# POWER-DCDC.net
KiCad netlist of a schematic drawn in EAGLE
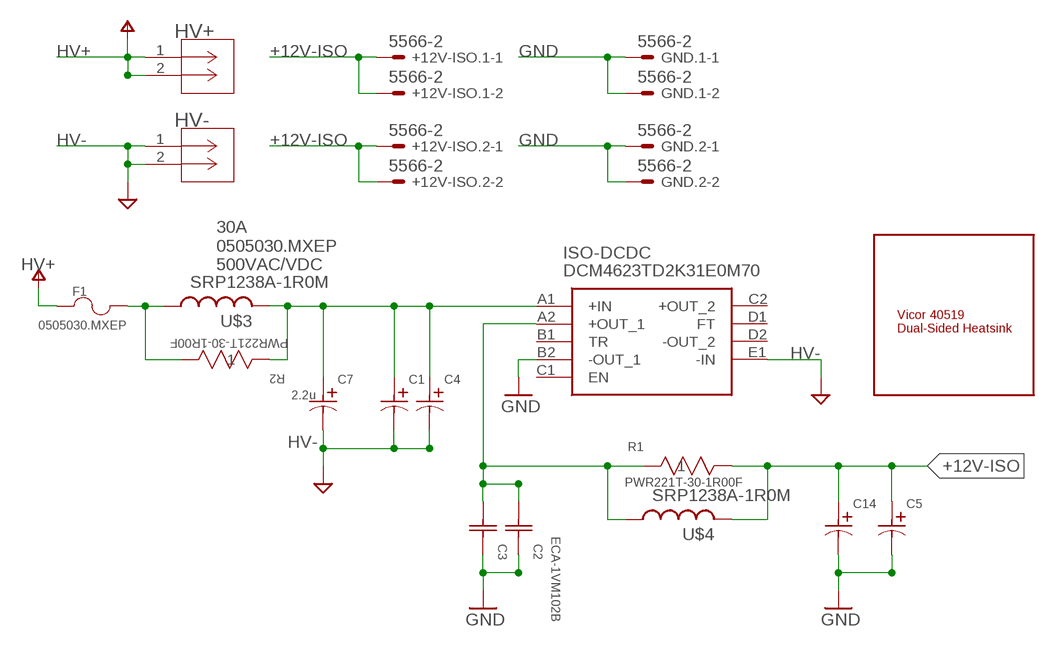
[diagram p0: schematic, sheet 1]

(export (version "E")
  (design (tool "Eeschema 10.0.6"))
  (components
    (comp (ref "+12V-ISO.1")
      (value "5566-2")
      (footprint "eagle-import:5566-2")
      (fields (field (name "MF") "MOLEX"))
      (libsource (lib "eagle-import") (part "5566-2"))
    )
    (comp (ref "+12V-ISO.2")
      (value "5566-2")
      (footprint "eagle-import:5566-2")
      (fields (field (name "MF") "MOLEX"))
      (libsource (lib "eagle-import") (part "5566-2"))
    )
    (comp (ref "C1")
      (value "ECA-2WHG2R2")
      (footprint "eagle-import:PCAP_10X125")
      (fields (field (name "MANUFACTURER_PART_NUMBER") "ECA2WHG2R2"))
      (libsource (lib "eagle-import") (part "ECA-2WHG2R2"))
    )
    (comp (ref "C2")
      (value "ECA-1VM102B")
      (footprint "eagle-import:CAP_PAN_12.5X20")
      (fields (field (name "MANUFACTURER_PART_NUMBER") "ECA1VM102B"))
      (libsource (lib "eagle-import") (part "ECA-1VM102B"))
    )
    (comp (ref "C3")
      (value "ECA-1VM102B")
      (footprint "eagle-import:CAP_PAN_12.5X20")
      (fields (field (name "MANUFACTURER_PART_NUMBER") "ECA1VM102B"))
      (libsource (lib "eagle-import") (part "ECA-1VM102B"))
    )
    (comp (ref "C4")
      (value "ECA-2WHG2R2")
      (footprint "eagle-import:PCAP_10X125")
      (fields (field (name "MANUFACTURER_PART_NUMBER") "ECA2WHG2R2"))
      (libsource (lib "eagle-import") (part "ECA-2WHG2R2"))
    )
    (comp (ref "C5")
      (value "ECA-2WHG2R2")
      (footprint "eagle-import:PCAP_10X125")
      (fields (field (name "MANUFACTURER_PART_NUMBER") "ECA2WHG2R2"))
      (libsource (lib "eagle-import") (part "ECA-2WHG2R2"))
    )
    (comp (ref "C7")
      (value "2.2u")
      (footprint "eagle-import:PCAP_10X125")
      (fields (field (name "MANUFACTURER_PART_NUMBER") "ECA2WHG2R2"))
      (libsource (lib "eagle-import") (part "ECA-2WHG2R2"))
    )
    (comp (ref "C14")
      (value "ECA-2WHG2R2")
      (footprint "eagle-import:PCAP_10X125")
      (fields (field (name "MANUFACTURER_PART_NUMBER") "ECA2WHG2R2"))
      (libsource (lib "eagle-import") (part "ECA-2WHG2R2"))
    )
    (comp (ref "F1")
      (value "0505030.MXEP")
      (footprint "eagle-import:0505030.MXEP")
      (libsource (lib "eagle-import") (part "0505030.MXEP"))
    )
    (comp (ref "GND.1")
      (value "5566-2")
      (footprint "eagle-import:5566-2")
      (fields (field (name "MF") "MOLEX"))
      (libsource (lib "eagle-import") (part "5566-2"))
    )
    (comp (ref "GND.2")
      (value "5566-2")
      (footprint "eagle-import:5566-2")
      (fields (field (name "MF") "MOLEX"))
      (libsource (lib "eagle-import") (part "5566-2"))
    )
    (comp (ref "HEATSINK")
      (value "DCMHEATSINK")
      (footprint "eagle-import:DCMHEATSINK")
      (libsource (lib "eagle-import") (part "DCMHEATSINK"))
    )
    (comp (ref "HV+")
      (value "2P_1-770166-0")
      (footprint "eagle-import:CON2_1X2_P163_VMNL-1MTG")
      (fields (field (name "MANUFACTURER_PART_NUMBER") "17701660"))
      (libsource (lib "eagle-import") (part "2P_1-770166-0"))
    )
    (comp (ref "HV-")
      (value "2P_1-770166-0")
      (footprint "eagle-import:CON2_1X2_P163_VMNL-1MTG")
      (fields (field (name "MANUFACTURER_PART_NUMBER") "17701660"))
      (libsource (lib "eagle-import") (part "2P_1-770166-0"))
    )
    (comp (ref "ISO-DCDC")
      (value "DCM4623TD2K31E0M70")
      (footprint "eagle-import:DCM4623TD2N17C8T70")
      (fields (field (name "MOUSER_PART_NUMBER") "492-DCM4623D2K31E0M7"))
      (libsource (lib "eagle-import") (part "DCM4623TD2K31E0M70"))
    )
    (comp (ref "R1")
      (value "PWR221T-30-1R00F")
      (footprint "eagle-import:BO_PWR221T")
      (fields (field (name "MANUFACTURER_PART_NUMBER") "PWR221T301R00F"))
      (libsource (lib "eagle-import") (part "PWR221T-30-1R00F"))
    )
    (comp (ref "R2")
      (value "PWR221T-30-1R00F")
      (footprint "eagle-import:BO_PWR221T")
      (fields (field (name "MANUFACTURER_PART_NUMBER") "PWR221T301R00F"))
      (libsource (lib "eagle-import") (part "PWR221T-30-1R00F"))
    )
    (comp (ref "U$3")
      (value "SRP1238A-1R0M")
      (footprint "eagle-import:SRP1238A-R22M")
      (libsource (lib "eagle-import") (part "SRP1238A-1R0M"))
    )
    (comp (ref "U$4")
      (value "SRP1238A-1R0M")
      (footprint "eagle-import:SRP1238A-R22M")
      (libsource (lib "eagle-import") (part "SRP1238A-1R0M"))
    )
  )
  (nets
    (net (code "1") (name "+12V-ISO") (class "Default")
      (node (ref "+12V-ISO.1") (pin "1") (pinfunction "S_1") (pintype "passive"))
      (node (ref "+12V-ISO.1") (pin "2") (pinfunction "S_2") (pintype "passive"))
      (node (ref "+12V-ISO.2") (pin "1") (pinfunction "S_1") (pintype "passive"))
      (node (ref "+12V-ISO.2") (pin "2") (pinfunction "S_2") (pintype "passive"))
      (node (ref "C14") (pin "1") (pinfunction "1_1") (pintype "passive"))
      (node (ref "C5") (pin "1") (pinfunction "1_1") (pintype "passive"))
      (node (ref "R1") (pin "2") (pinfunction "2_2") (pintype "passive"))
      (node (ref "U$4") (pin "2") (pinfunction "2_2") (pintype "passive"))
    )
    (net (code "2") (name "AGND") (class "Default")
      (node (ref "C1") (pin "2") (pinfunction "2_2") (pintype "passive"))
      (node (ref "C4") (pin "2") (pinfunction "2_2") (pintype "passive"))
      (node (ref "C7") (pin "2") (pinfunction "2_2") (pintype "passive"))
      (node (ref "HV-") (pin "1") (pinfunction "1_1") (pintype "passive"))
      (node (ref "HV-") (pin "2") (pinfunction "2_2") (pintype "passive"))
      (node (ref "ISO-DCDC") (pin "E1") (pinfunction "-IN_E1") (pintype "bidirectional"))
    )
    (net (code "3") (name "GND") (class "Default")
      (node (ref "C14") (pin "2") (pinfunction "2_2") (pintype "passive"))
      (node (ref "C2") (pin "2") (pinfunction "2_2") (pintype "passive"))
      (node (ref "C3") (pin "2") (pinfunction "2_2") (pintype "passive"))
      (node (ref "C5") (pin "2") (pinfunction "2_2") (pintype "passive"))
      (node (ref "GND.1") (pin "1") (pinfunction "S_1") (pintype "passive"))
      (node (ref "GND.1") (pin "2") (pinfunction "S_2") (pintype "passive"))
      (node (ref "GND.2") (pin "1") (pinfunction "S_1") (pintype "passive"))
      (node (ref "GND.2") (pin "2") (pinfunction "S_2") (pintype "passive"))
      (node (ref "ISO-DCDC") (pin "B2") (pinfunction "-OUT_1_B2") (pintype "bidirectional"))
    )
    (net (code "4") (name "Net-(F1-Pad2)") (class "Default")
      (node (ref "F1") (pin "2") (pinfunction "2_2") (pintype "passive"))
      (node (ref "R2") (pin "2") (pinfunction "2_2") (pintype "passive"))
      (node (ref "U$3") (pin "1") (pinfunction "1_1") (pintype "passive"))
    )
    (net (code "5") (name "Net-(ISO-DCDC-+IN)") (class "Default")
      (node (ref "C1") (pin "1") (pinfunction "1_1") (pintype "passive"))
      (node (ref "C4") (pin "1") (pinfunction "1_1") (pintype "passive"))
      (node (ref "C7") (pin "1") (pinfunction "1_1") (pintype "passive"))
      (node (ref "ISO-DCDC") (pin "A1") (pinfunction "+IN_A1") (pintype "bidirectional"))
      (node (ref "R2") (pin "1") (pinfunction "1_1") (pintype "passive"))
      (node (ref "U$3") (pin "2") (pinfunction "2_2") (pintype "passive"))
    )
    (net (code "6") (name "Net-(ISO-DCDC-+OUT_1)") (class "Default")
      (node (ref "C2") (pin "1") (pinfunction "1_1") (pintype "passive"))
      (node (ref "C3") (pin "1") (pinfunction "1_1") (pintype "passive"))
      (node (ref "ISO-DCDC") (pin "A2") (pinfunction "+OUT_1_A2") (pintype "bidirectional"))
      (node (ref "R1") (pin "1") (pinfunction "1_1") (pintype "passive"))
      (node (ref "U$4") (pin "1") (pinfunction "1_1") (pintype "passive"))
    )
    (net (code "7") (name "V+") (class "Default")
      (node (ref "F1") (pin "1") (pinfunction "1_1") (pintype "passive"))
      (node (ref "HV+") (pin "1") (pinfunction "1_1") (pintype "passive"))
      (node (ref "HV+") (pin "2") (pinfunction "2_2") (pintype "passive"))
    )
    (net (code "8") (name "unconnected-(ISO-DCDC-+OUT_2-PadC2)") (class "Default")
      (node (ref "ISO-DCDC") (pin "C2") (pinfunction "+OUT_2_C2") (pintype "bidirectional"))
    )
    (net (code "9") (name "unconnected-(ISO-DCDC--OUT_2-PadD2)") (class "Default")
      (node (ref "ISO-DCDC") (pin "D2") (pinfunction "-OUT_2_D2") (pintype "bidirectional"))
    )
    (net (code "10") (name "unconnected-(ISO-DCDC-EN-PadC1)") (class "Default")
      (node (ref "ISO-DCDC") (pin "C1") (pinfunction "EN_C1") (pintype "bidirectional"))
    )
    (net (code "11") (name "unconnected-(ISO-DCDC-FT-PadD1)") (class "Default")
      (node (ref "ISO-DCDC") (pin "D1") (pinfunction "FT_D1") (pintype "bidirectional"))
    )
    (net (code "12") (name "unconnected-(ISO-DCDC-TR-PadB1)") (class "Default")
      (node (ref "ISO-DCDC") (pin "B1") (pinfunction "TR_B1") (pintype "bidirectional"))
    )
  )
)
